# LEDs_0805.net
KiCad netlist of a schematic drawn in Altium Designer
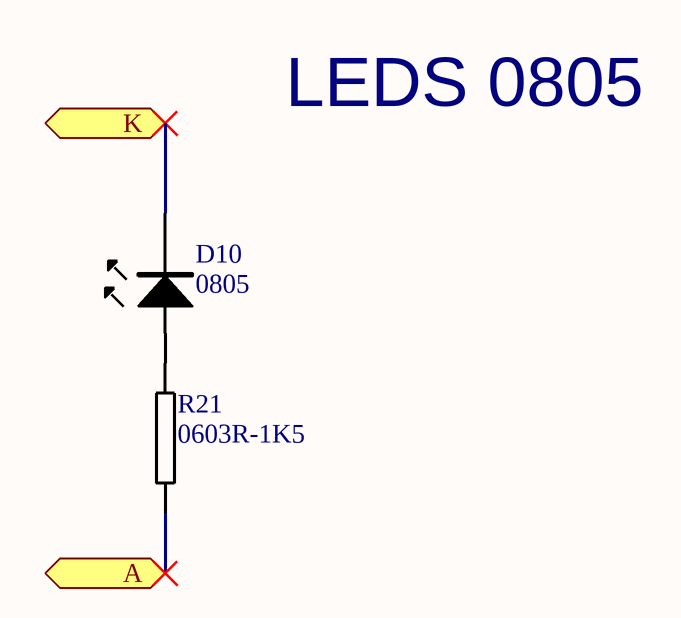
[diagram p0: LEDs 0805.SchDoc]

(export (version "E")
  (design (tool "Eeschema 10.0.6"))
  (components
    (comp (ref "D10")
      (value "0805")
      (footprint "0805LED")
      (libsource (lib "RVA_LED_SMD_0805") (part "0805_LED"))
    )
    (comp (ref "R21")
      (value "0603R-1K5")
      (footprint "0603R-1k5")
      (description "GENERIC RESISTOR 0603")
      (fields (field (name "MANUFACTURER PART NUMBER") "RMCF 1/16 15K 1% R") (field (name "TOLERANCE") "±1%"))
      (libsource (lib "RVA_Altium_Library") (part "0603R-1K5"))
    )
  )
  (nets
    (net (code "1") (name "/A") (class "Default") (node (ref "R21") (pin "2") (pintype "passive+no_connect")))
    (net (code "2") (name "/K") (class "Default") (node (ref "D10") (pin "K") (pintype "passive+no_connect")))
    (net (code "3") (name "Net-(D10-PadA)") (class "Default")
      (node (ref "D10") (pin "A") (pintype "passive"))
      (node (ref "R21") (pin "1") (pintype "passive"))
    )
  )
)
